# 555-dev-2.net
KiCad netlist of a schematic drawn in EAGLE
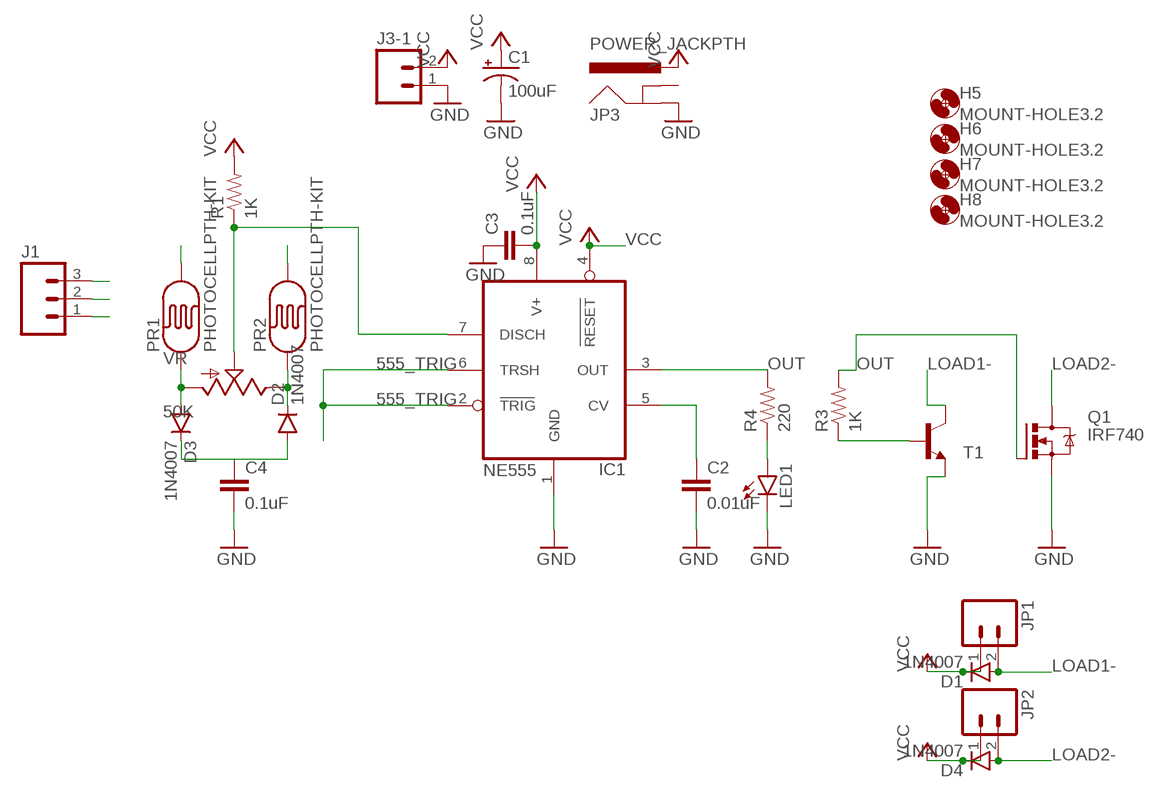
[diagram p0: schematic, sheet 1]

(export (version "E")
  (design (tool "Eeschema 10.0.6"))
  (components
    (comp (ref "C1")
      (value "100uF")
      (footprint "eagle-import:CPOL-RADIAL-100UF-25V")
      (libsource (lib "eagle-import") (part "CAP_POLPTH1"))
    )
    (comp (ref "C2")
      (value "0.01uF")
      (footprint "eagle-import:CAP-PTH-SMALL")
      (libsource (lib "eagle-import") (part "CAPPTH"))
    )
    (comp (ref "C3")
      (value "0.1uF")
      (footprint "eagle-import:CAP-PTH-SMALL")
      (libsource (lib "eagle-import") (part "CAPPTH"))
    )
    (comp (ref "C4")
      (value "0.1uF")
      (footprint "eagle-import:CAP-PTH-SMALL")
      (libsource (lib "eagle-import") (part "CAPPTH"))
    )
    (comp (ref "D1")
      (value "1N4007")
      (footprint "eagle-import:DIODE-1N4148-KIT")
      (libsource (lib "eagle-import") (part "DIODEKIT"))
    )
    (comp (ref "D2")
      (value "1N4007")
      (footprint "eagle-import:DIODE-1N4148-KIT")
      (libsource (lib "eagle-import") (part "DIODEKIT"))
    )
    (comp (ref "D3")
      (value "1N4007")
      (footprint "eagle-import:DIODE-1N4148-KIT")
      (libsource (lib "eagle-import") (part "DIODEKIT"))
    )
    (comp (ref "D4")
      (value "1N4007")
      (footprint "eagle-import:DIODE-1N4148-KIT")
      (libsource (lib "eagle-import") (part "DIODEKIT"))
    )
    (comp (ref "H5")
      (value "MOUNT-HOLE3.2")
      (footprint "eagle-import:3,2")
      (libsource (lib "eagle-import") (part "MOUNT-HOLE3.2"))
    )
    (comp (ref "H6")
      (value "MOUNT-HOLE3.2")
      (footprint "eagle-import:3,2")
      (libsource (lib "eagle-import") (part "MOUNT-HOLE3.2"))
    )
    (comp (ref "H7")
      (value "MOUNT-HOLE3.2")
      (footprint "eagle-import:3,2")
      (libsource (lib "eagle-import") (part "MOUNT-HOLE3.2"))
    )
    (comp (ref "H8")
      (value "MOUNT-HOLE3.2")
      (footprint "eagle-import:3,2")
      (libsource (lib "eagle-import") (part "MOUNT-HOLE3.2"))
    )
    (comp (ref "IC1")
      (value "NE555")
      (footprint "eagle-import:DIL08")
      (libsource (lib "eagle-import") (part "TLC555"))
    )
    (comp (ref "J1")
      (value "M03PTH")
      (footprint "eagle-import:1X03")
      (libsource (lib "eagle-import") (part "M03PTH"))
    )
    (comp (ref "J3-1")
      (value "M02PTH")
      (footprint "eagle-import:1X02")
      (libsource (lib "eagle-import") (part "M02PTH"))
    )
    (comp (ref "JP1")
      (value "M023.5MM-NO_SILK")
      (footprint "eagle-import:SCREWTERMINAL-3.5MM-2-NS")
      (libsource (lib "eagle-import") (part "M023.5MM-NO_SILK"))
    )
    (comp (ref "JP2")
      (value "M023.5MM-NO_SILK")
      (footprint "eagle-import:SCREWTERMINAL-3.5MM-2-NS")
      (libsource (lib "eagle-import") (part "M023.5MM-NO_SILK"))
    )
    (comp (ref "JP3")
      (value "POWER_JACKPTH")
      (footprint "eagle-import:POWER_JACK_PTH")
      (libsource (lib "eagle-import") (part "POWER_JACKPTH"))
    )
    (comp (ref "LED1")
      (value "LED5MM-KIT")
      (footprint "eagle-import:LED5MM-KIT")
      (libsource (lib "eagle-import") (part "LED5MM-KIT"))
    )
    (comp (ref "PR1")
      (value "PHOTOCELLPTH-KIT")
      (footprint "eagle-import:PHOTOCELL-KIT")
      (libsource (lib "eagle-import") (part "PHOTOCELLPTH-KIT"))
    )
    (comp (ref "PR2")
      (value "PHOTOCELLPTH-KIT")
      (footprint "eagle-import:PHOTOCELL-KIT")
      (libsource (lib "eagle-import") (part "PHOTOCELLPTH-KIT"))
    )
    (comp (ref "Q1")
      (value "IRF740")
      (footprint "eagle-import:TO220BV")
      (libsource (lib "eagle-import") (part "IRF740"))
    )
    (comp (ref "R1")
      (value "1K")
      (footprint "eagle-import:AXIAL-0.4")
      (libsource (lib "eagle-import") (part "RESISTORPTH-1/4W"))
    )
    (comp (ref "R3")
      (value "1K")
      (footprint "eagle-import:AXIAL-0.4")
      (libsource (lib "eagle-import") (part "RESISTORPTH-1/4W"))
    )
    (comp (ref "R4")
      (value "220")
      (footprint "eagle-import:AXIAL-0.4")
      (libsource (lib "eagle-import") (part "RESISTORPTH-1/4W"))
    )
    (comp (ref "T1")
      (value "2N2222")
      (footprint "eagle-import:TO92-EBC-OVAL")
      (libsource (lib "eagle-import") (part "2N2222"))
    )
    (comp (ref "VR")
      (value "50K")
      (footprint "eagle-import:ALPS_POT_KIT")
      (libsource (lib "eagle-import") (part "POTALPS-KIT"))
    )
  )
  (nets
    (net (code "1") (name "/555_DISCH") (class "Default")
      (node (ref "IC1") (pin "7") (pinfunction "DISCH_7") (pintype "input"))
      (node (ref "J1") (pin "2") (pinfunction "2_2") (pintype "passive"))
      (node (ref "R1") (pin "P$1") (pinfunction "1_P$1") (pintype "passive"))
      (node (ref "VR") (pin "P$2") (pinfunction "S_P$2") (pintype "passive"))
    )
    (net (code "2") (name "/555_TRIG") (class "Default")
      (node (ref "IC1") (pin "2") (pinfunction "TRIG_2") (pintype "bidirectional"))
      (node (ref "IC1") (pin "6") (pinfunction "TRSH_6") (pintype "input"))
    )
    (net (code "3") (name "/LOAD1-") (class "Default")
      (node (ref "D1") (pin "A") (pinfunction "A_A") (pintype "passive"))
      (node (ref "JP1") (pin "2") (pinfunction "2_2") (pintype "passive"))
      (node (ref "T1") (pin "C") (pinfunction "C_C") (pintype "passive"))
    )
    (net (code "4") (name "/LOAD2-") (class "Default")
      (node (ref "D4") (pin "A") (pinfunction "A_A") (pintype "passive"))
      (node (ref "JP2") (pin "2") (pinfunction "2_2") (pintype "passive"))
      (node (ref "Q1") (pin "D") (pinfunction "D_D") (pintype "passive"))
    )
    (net (code "5") (name "/OUT") (class "Default")
      (node (ref "IC1") (pin "3") (pinfunction "OUT_3") (pintype "output"))
      (node (ref "Q1") (pin "G") (pinfunction "G_G") (pintype "passive"))
      (node (ref "R3") (pin "P$2") (pinfunction "2_P$2") (pintype "passive"))
      (node (ref "R4") (pin "P$2") (pinfunction "2_P$2") (pintype "passive"))
    )
    (net (code "6") (name "/PR1") (class "Default")
      (node (ref "J1") (pin "1") (pinfunction "1_1") (pintype "passive"))
      (node (ref "PR1") (pin "2") (pinfunction "P$2_2") (pintype "bidirectional"))
    )
    (net (code "7") (name "/PR2") (class "Default")
      (node (ref "J1") (pin "3") (pinfunction "3_3") (pintype "passive"))
      (node (ref "PR2") (pin "2") (pinfunction "P$2_2") (pintype "bidirectional"))
    )
    (net (code "8") (name "GND") (class "Default")
      (node (ref "C1") (pin "2") (pinfunction "-_2") (pintype "passive"))
      (node (ref "C2") (pin "2") (pinfunction "2_2") (pintype "passive"))
      (node (ref "C3") (pin "1") (pinfunction "1_1") (pintype "passive"))
      (node (ref "C4") (pin "2") (pinfunction "2_2") (pintype "passive"))
      (node (ref "IC1") (pin "1") (pinfunction "GND_1") (pintype "power_in"))
      (node (ref "J3-1") (pin "1") (pinfunction "1_1") (pintype "passive"))
      (node (ref "JP3") (pin "GND") (pinfunction "GND_GND") (pintype "bidirectional"))
      (node (ref "LED1") (pin "K") (pinfunction "C_K") (pintype "passive"))
      (node (ref "Q1") (pin "S") (pinfunction "S_S") (pintype "passive"))
      (node (ref "T1") (pin "E") (pinfunction "E_E") (pintype "passive"))
    )
    (net (code "9") (name "Net-(C4-Pad1)") (class "Default")
      (node (ref "C4") (pin "1") (pinfunction "1_1") (pintype "passive"))
      (node (ref "D2") (pin "A") (pinfunction "A_A") (pintype "passive"))
      (node (ref "D3") (pin "C") (pinfunction "C_C") (pintype "passive"))
    )
    (net (code "10") (name "Net-(IC1-CV)") (class "Default")
      (node (ref "C2") (pin "1") (pinfunction "1_1") (pintype "passive"))
      (node (ref "IC1") (pin "5") (pinfunction "CV_5") (pintype "passive"))
    )
    (net (code "11") (name "Net-(PR1-P$1)") (class "Default")
      (node (ref "D3") (pin "A") (pinfunction "A_A") (pintype "passive"))
      (node (ref "PR1") (pin "1") (pinfunction "P$1_1") (pintype "bidirectional"))
      (node (ref "VR") (pin "P$3") (pinfunction "A_P$3") (pintype "passive"))
    )
    (net (code "12") (name "Net-(PR2-P$1)") (class "Default")
      (node (ref "D2") (pin "C") (pinfunction "C_C") (pintype "passive"))
      (node (ref "PR2") (pin "1") (pinfunction "P$1_1") (pintype "bidirectional"))
      (node (ref "VR") (pin "P$1") (pinfunction "E_P$1") (pintype "passive"))
    )
    (net (code "13") (name "Net-(R3-1)") (class "Default")
      (node (ref "R3") (pin "P$1") (pinfunction "1_P$1") (pintype "passive"))
      (node (ref "T1") (pin "B") (pinfunction "B_B") (pintype "passive"))
    )
    (net (code "14") (name "Net-(R4-1)") (class "Default")
      (node (ref "LED1") (pin "A") (pinfunction "A_A") (pintype "passive"))
      (node (ref "R4") (pin "P$1") (pinfunction "1_P$1") (pintype "passive"))
    )
    (net (code "15") (name "VCC") (class "Default")
      (node (ref "C1") (pin "1") (pinfunction "+_1") (pintype "passive"))
      (node (ref "C3") (pin "2") (pinfunction "2_2") (pintype "passive"))
      (node (ref "D1") (pin "C") (pinfunction "C_C") (pintype "passive"))
      (node (ref "D4") (pin "C") (pinfunction "C_C") (pintype "passive"))
      (node (ref "IC1") (pin "4") (pinfunction "RESET_4") (pintype "input"))
      (node (ref "IC1") (pin "8") (pinfunction "V+_8") (pintype "power_in"))
      (node (ref "J3-1") (pin "2") (pinfunction "2_2") (pintype "passive"))
      (node (ref "JP1") (pin "1") (pinfunction "1_1") (pintype "passive"))
      (node (ref "JP2") (pin "1") (pinfunction "1_1") (pintype "passive"))
      (node (ref "JP3") (pin "PWR") (pinfunction "PWR_PWR") (pintype "bidirectional"))
      (node (ref "R1") (pin "P$2") (pinfunction "2_P$2") (pintype "passive"))
    )
    (net (code "16") (name "unconnected-(JP3-PadGNDBREAK)") (class "Default")
      (node (ref "JP3") (pin "GNDBREAK") (pinfunction "GNDBREAK_GNDBREAK") (pintype "bidirectional"))
    )
  )
)
